# h.net
KiCad netlist of a schematic drawn in Altium Designer
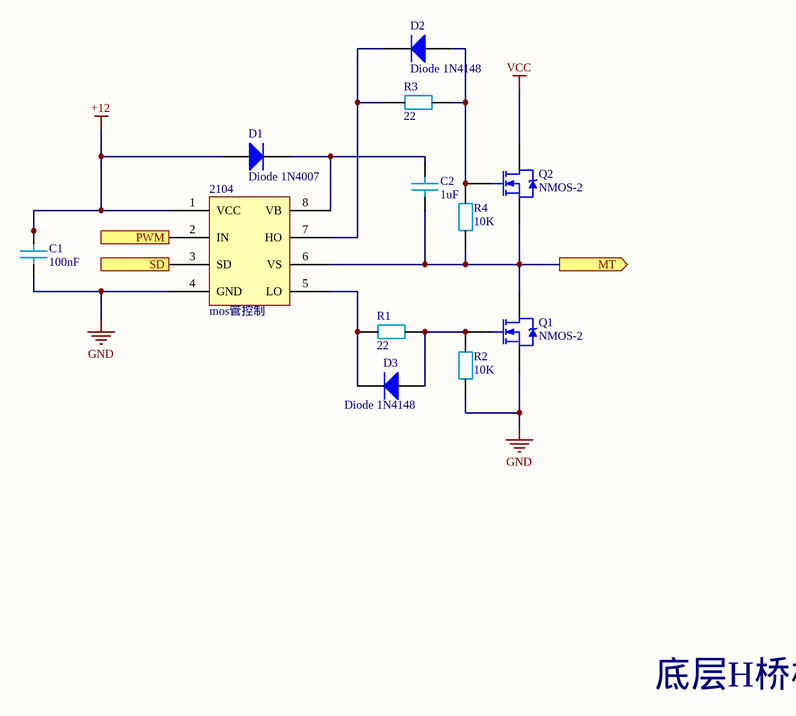
[diagram p0: h桥.SchDoc]

(export (version "E")
  (design (tool "Eeschema 10.0.6"))
  (components
    (comp (ref "2104") (value "mos管控制") (footprint "SOP8") (libsource (lib "elin私人订制") (part "eg2104")))
    (comp (ref "C1") (value "100nF") (footprint "0805_C") (libsource (lib "elin私人订制") (part "C")))
    (comp (ref "C2") (value "1uF") (footprint "0805_C") (libsource (lib "elin私人订制") (part "C")))
    (comp (ref "D1")
      (value "Diode 1N4007")
      (footprint "DO-41")
      (description "1 Amp General Purpose Rectifier")
      (fields (field (name "PUBLISHER") "Altium Limited"))
      (libsource (lib "Miscellaneous Devices") (part "Diode 1N4007"))
    )
    (comp (ref "D2")
      (value "Diode 1N4148")
      (footprint "DO-35")
      (description "High Conductance Fast Diode")
      (fields (field (name "PUBLISHER") "Altium Limited"))
      (libsource (lib "Miscellaneous Devices") (part "Diode 1N4148"))
    )
    (comp (ref "D3")
      (value "Diode 1N4148")
      (footprint "DO-35")
      (description "High Conductance Fast Diode")
      (fields (field (name "PUBLISHER") "Altium Limited"))
      (libsource (lib "Miscellaneous Devices") (part "Diode 1N4148"))
    )
    (comp (ref "Q1")
      (value "NMOS-2")
      (footprint "LC-TO-252-2")
      (description "N-Channel Power MOSFET")
      (fields (field (name "PUBLISHER") "Altium Limited"))
      (libsource (lib "Miscellaneous Devices") (part "NMOS-2"))
    )
    (comp (ref "Q2")
      (value "NMOS-2")
      (footprint "LC-TO-252-2-180")
      (description "N-Channel Power MOSFET")
      (fields (field (name "PUBLISHER") "Altium Limited"))
      (libsource (lib "Miscellaneous Devices") (part "NMOS-2"))
    )
    (comp (ref "R1") (value "22") (footprint "0805_R") (libsource (lib "elin私人订制") (part "R")))
    (comp (ref "R2") (value "10K") (footprint "0805_R") (libsource (lib "elin私人订制") (part "R")))
    (comp (ref "R3") (value "22") (footprint "0805_R") (libsource (lib "elin私人订制") (part "R")))
    (comp (ref "R4") (value "10K") (footprint "0805_R") (libsource (lib "elin私人订制") (part "R")))
  )
  (nets
    (net (code "1") (name "+12") (class "Default")
      (node (ref "2104") (pin "1") (pinfunction "VCC_1") (pintype "passive"))
      (node (ref "C1") (pin "2") (pinfunction "2_2") (pintype "passive"))
      (node (ref "D1") (pin "1") (pinfunction "A_1") (pintype "passive"))
    )
    (net (code "2") (name "/MT") (class "Default")
      (node (ref "2104") (pin "6") (pinfunction "VS_6") (pintype "passive"))
      (node (ref "C2") (pin "1") (pinfunction "1_1") (pintype "passive"))
      (node (ref "Q1") (pin "2") (pinfunction "D_2") (pintype "passive"))
      (node (ref "Q2") (pin "3") (pinfunction "S_3") (pintype "passive"))
      (node (ref "R4") (pin "1") (pinfunction "1_1") (pintype "passive"))
    )
    (net (code "3") (name "/PWM") (class "Default")
      (node (ref "2104") (pin "2") (pinfunction "IN_2") (pintype "passive"))
    )
    (net (code "4") (name "/SD") (class "Default")
      (node (ref "2104") (pin "3") (pinfunction "SD_3") (pintype "passive"))
    )
    (net (code "5") (name "GND") (class "Default")
      (node (ref "2104") (pin "4") (pinfunction "GND_4") (pintype "passive"))
      (node (ref "C1") (pin "1") (pinfunction "1_1") (pintype "passive"))
      (node (ref "Q1") (pin "3") (pinfunction "S_3") (pintype "passive"))
      (node (ref "R2") (pin "2") (pinfunction "2_2") (pintype "passive"))
    )
    (net (code "6") (name "Net-(2104-HO)") (class "Default")
      (node (ref "2104") (pin "7") (pinfunction "HO_7") (pintype "passive"))
      (node (ref "D2") (pin "2") (pinfunction "K_2") (pintype "passive"))
      (node (ref "R3") (pin "1") (pinfunction "1_1") (pintype "passive"))
    )
    (net (code "7") (name "Net-(2104-LO)") (class "Default")
      (node (ref "2104") (pin "5") (pinfunction "LO_5") (pintype "passive"))
      (node (ref "D3") (pin "2") (pinfunction "K_2") (pintype "passive"))
      (node (ref "R1") (pin "1") (pinfunction "1_1") (pintype "passive"))
    )
    (net (code "8") (name "Net-(2104-VB)") (class "Default")
      (node (ref "2104") (pin "8") (pinfunction "VB_8") (pintype "passive"))
      (node (ref "C2") (pin "2") (pinfunction "2_2") (pintype "passive"))
      (node (ref "D1") (pin "2") (pinfunction "K_2") (pintype "passive"))
    )
    (net (code "9") (name "Net-(D2-A)") (class "Default")
      (node (ref "D2") (pin "1") (pinfunction "A_1") (pintype "passive"))
      (node (ref "Q2") (pin "1") (pinfunction "G_1") (pintype "passive"))
      (node (ref "R3") (pin "2") (pinfunction "2_2") (pintype "passive"))
      (node (ref "R4") (pin "2") (pinfunction "2_2") (pintype "passive"))
    )
    (net (code "10") (name "Net-(D3-A)") (class "Default")
      (node (ref "D3") (pin "1") (pinfunction "A_1") (pintype "passive"))
      (node (ref "Q1") (pin "1") (pinfunction "G_1") (pintype "passive"))
      (node (ref "R1") (pin "2") (pinfunction "2_2") (pintype "passive"))
      (node (ref "R2") (pin "1") (pinfunction "1_1") (pintype "passive"))
    )
    (net (code "11") (name "VCC") (class "Default")
      (node (ref "Q2") (pin "2") (pinfunction "D_2") (pintype "passive"))
    )
  )
)
